# Power_managment.net
KiCad netlist of a schematic drawn in Altium Designer
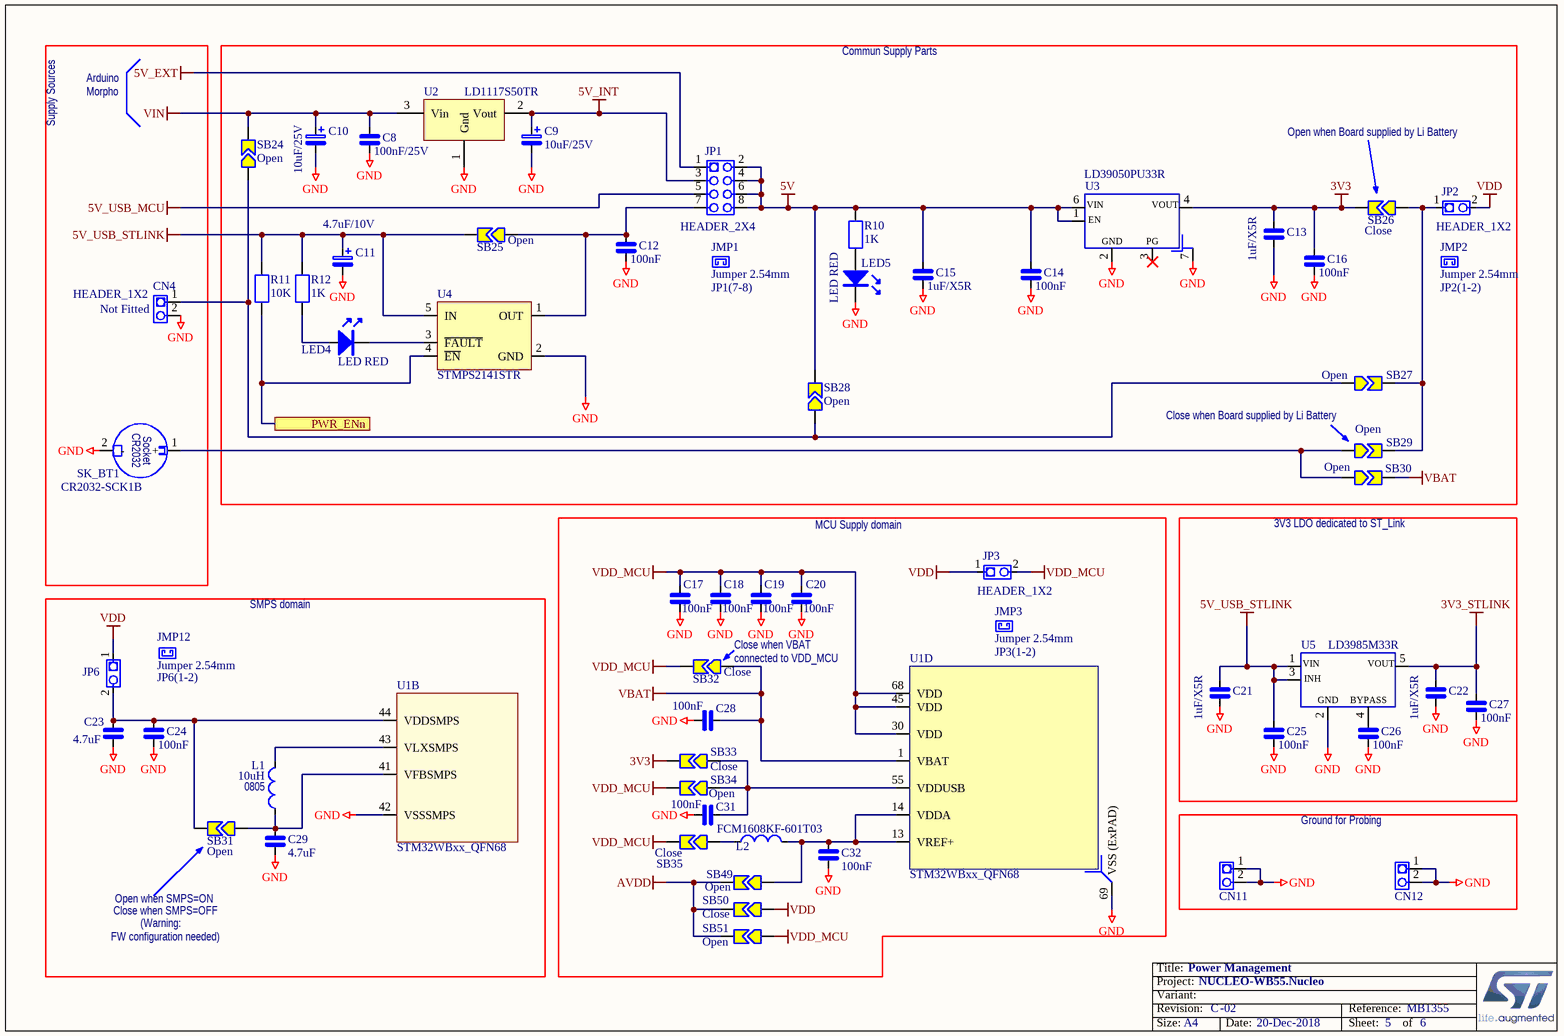
[diagram p0: Power_managment.SchDoc]

(export (version "E")
  (design (tool "Eeschema 10.0.6"))
  (components
    (comp (ref "C8")
      (value "100nF/25V")
      (footprint "0402_CAP_NPOL")
      (description "Capacitor_not polarized")
      (libsource (lib "ST_Lib3D") (part "CAP_NPOL"))
    )
    (comp (ref "C9")
      (value "10uF/25V")
      (footprint "1210_CAP_POL")
      (description "Condensateur_polarise")
      (libsource (lib "Passive") (part "CAP_POL"))
    )
    (comp (ref "C10")
      (value "10uF/25V")
      (footprint "1210_CAP_POL")
      (description "Condensateur_polarise")
      (libsource (lib "Passive") (part "CAP_POL"))
    )
    (comp (ref "C11")
      (value "4.7uF/10V")
      (footprint "1210_CAP_POL")
      (description "Condensateur_polarise")
      (libsource (lib "Passive") (part "CAP_POL"))
    )
    (comp (ref "C12")
      (value "100nF")
      (footprint "0402_CAP_NPOL")
      (description "Capacitor_not polarized")
      (libsource (lib "ST_Lib3D") (part "CAP_NPOL"))
    )
    (comp (ref "C13")
      (value "1uF/X5R")
      (footprint "0603_CAP_NPOL")
      (description "Capacitor_not polarized")
      (libsource (lib "ST_Lib3D") (part "CAP_NPOL"))
    )
    (comp (ref "C14")
      (value "100nF")
      (footprint "0402_CAP_NPOL")
      (description "Capacitor_not polarized")
      (libsource (lib "ST_Lib3D") (part "CAP_NPOL"))
    )
    (comp (ref "C15")
      (value "1uF/X5R")
      (footprint "0603_CAP_NPOL")
      (description "Capacitor_not polarized")
      (libsource (lib "ST_Lib3D") (part "CAP_NPOL"))
    )
    (comp (ref "C16")
      (value "100nF")
      (footprint "0402_CAP_NPOL")
      (description "Capacitor_not polarized")
      (libsource (lib "ST_Lib3D") (part "CAP_NPOL"))
    )
    (comp (ref "C17")
      (value "100nF")
      (footprint "0402_CAP_NPOL")
      (description "Capacitor_not polarized")
      (libsource (lib "ST_Lib3D") (part "CAP_NPOL"))
    )
    (comp (ref "C18")
      (value "100nF")
      (footprint "0402_CAP_NPOL")
      (description "Capacitor_not polarized")
      (libsource (lib "ST_Lib3D") (part "CAP_NPOL"))
    )
    (comp (ref "C19")
      (value "100nF")
      (footprint "0402_CAP_NPOL")
      (description "Capacitor_not polarized")
      (libsource (lib "ST_Lib3D") (part "CAP_NPOL"))
    )
    (comp (ref "C20")
      (value "100nF")
      (footprint "0402_CAP_NPOL")
      (description "Capacitor_not polarized")
      (libsource (lib "ST_Lib3D") (part "CAP_NPOL"))
    )
    (comp (ref "C21")
      (value "1uF/X5R")
      (footprint "0603_CAP_NPOL")
      (description "Capacitor_not polarized")
      (libsource (lib "ST_Lib3D") (part "CAP_NPOL"))
    )
    (comp (ref "C22")
      (value "1uF/X5R")
      (footprint "0603_CAP_NPOL")
      (description "Capacitor_not polarized")
      (libsource (lib "ST_Lib3D") (part "CAP_NPOL"))
    )
    (comp (ref "C23")
      (value "4.7uF")
      (footprint "0402_CAP_NPOL")
      (description "Capacitor_not polarized")
      (libsource (lib "ST_Lib3D") (part "CAP_NPOL"))
    )
    (comp (ref "C24")
      (value "100nF")
      (footprint "0402_CAP_NPOL")
      (description "Capacitor_not polarized")
      (libsource (lib "ST_Lib3D") (part "CAP_NPOL"))
    )
    (comp (ref "C25")
      (value "100nF")
      (footprint "0402_CAP_NPOL")
      (description "Capacitor_not polarized")
      (libsource (lib "ST_Lib3D") (part "CAP_NPOL"))
    )
    (comp (ref "C26")
      (value "100nF")
      (footprint "0402_CAP_NPOL")
      (description "Capacitor_not polarized")
      (libsource (lib "ST_Lib3D") (part "CAP_NPOL"))
    )
    (comp (ref "C27")
      (value "100nF")
      (footprint "0402_CAP_NPOL")
      (description "Capacitor_not polarized")
      (libsource (lib "ST_Lib3D") (part "CAP_NPOL"))
    )
    (comp (ref "C28")
      (value "100nF")
      (footprint "0402_CAP_NPOL")
      (description "Capacitor_not polarized")
      (libsource (lib "ST_Lib3D") (part "CAP_NPOL"))
    )
    (comp (ref "C29")
      (value "4.7uF")
      (footprint "0402_CAP_NPOL")
      (description "Capacitor_not polarized")
      (libsource (lib "ST_Lib3D") (part "CAP_NPOL"))
    )
    (comp (ref "C31")
      (value "100nF")
      (footprint "0402_CAP_NPOL")
      (description "Capacitor_not polarized")
      (libsource (lib "ST_Lib3D") (part "CAP_NPOL"))
    )
    (comp (ref "C32")
      (value "100nF")
      (footprint "0402_CAP_NPOL")
      (description "Capacitor_not polarized")
      (libsource (lib "ST_Lib3D") (part "CAP_NPOL"))
    )
    (comp (ref "CN4")
      (value "HEADER_1X2")
      (footprint "Header NF 1x2x2.54 TH")
      (fields (field (name "FITTED") "Not Fitted"))
      (libsource (lib "Connector") (part "HEADER_1X2"))
    )
    (comp (ref "CN11")
      (value "HEADER_1X2")
      (footprint "Header M 1x2x2.54 TH V")
      (libsource (lib "Connector") (part "HEADER_1X2"))
    )
    (comp (ref "CN12")
      (value "HEADER_1X2")
      (footprint "Header M 1x2x2.54 TH V")
      (libsource (lib "Connector") (part "HEADER_1X2"))
    )
    (comp (ref "JMP1")
      (value "Jumper 2.54mm")
      (footprint "Jumper 2.54mm BLACK")
      (fields (field (name "DEFAULT") "JP1(7-8)"))
      (libsource (lib "Connector") (part "Jumper 2.54mm"))
    )
    (comp (ref "JMP2")
      (value "Jumper 2.54mm")
      (footprint "Jumper 2.54mm BLACK")
      (fields (field (name "DEFAULT") "JP2(1-2)"))
      (libsource (lib "Connector") (part "Jumper 2.54mm"))
    )
    (comp (ref "JMP3")
      (value "Jumper 2.54mm")
      (footprint "Jumper 2.54mm BLACK")
      (fields (field (name "DEFAULT") "JP3(1-2)"))
      (libsource (lib "Connector") (part "Jumper 2.54mm"))
    )
    (comp (ref "JMP12")
      (value "Jumper 2.54mm")
      (footprint "Jumper 2.54mm BLACK")
      (fields (field (name "DEFAULT") "JP6(1-2)"))
      (libsource (lib "Connector") (part "Jumper 2.54mm"))
    )
    (comp (ref "JP1")
      (value "HEADER_2X4")
      (footprint "Header M 2x4x2.54 TH V")
      (libsource (lib "Connector") (part "HEADER_2X4"))
    )
    (comp (ref "JP2")
      (value "HEADER_1X2")
      (footprint "Header M 1x2x2.54 TH V")
      (libsource (lib "Connector") (part "HEADER_1X2_L"))
    )
    (comp (ref "JP3")
      (value "HEADER_1X2")
      (footprint "Header M 1x2x2.54 TH V")
      (libsource (lib "Connector") (part "HEADER_1X2_L"))
    )
    (comp (ref "JP6")
      (value "HEADER_1X2")
      (footprint "Header M 1x2x2.54 TH V")
      (libsource (lib "Connector") (part "HEADER_1X2_L"))
    )
    (comp (ref "L1")
      (value "10uH")
      (footprint "0805_COIL")
      (description "Coil Wurtz 10uH ref: 74479777310A")
      (libsource (lib "Passive") (part "IND_74479777310A"))
    )
    (comp (ref "L2")
      (value "FCM1608KF-601T03")
      (footprint "0603_COIL")
      (libsource (lib "Passive") (part "IND_FCM1608KF-601T03"))
    )
    (comp (ref "LED4")
      (value "LED RED")
      (footprint "0603_LED_RED")
      (description "Light-Emitting Diode")
      (libsource (lib "Active") (part "LED"))
    )
    (comp (ref "LED5")
      (value "LED RED")
      (footprint "0603_LED_RED")
      (description "Light-Emitting Diode")
      (libsource (lib "Active") (part "LED"))
    )
    (comp (ref "R10")
      (value "1K")
      (footprint "0402_RES")
      (description "Resistor")
      (libsource (lib "Lib3D_Altium10_Schlib") (part "RES"))
    )
    (comp (ref "R11")
      (value "10K")
      (footprint "0402_RES")
      (description "Resistor")
      (libsource (lib "Lib3D_Altium10_Schlib") (part "RES"))
    )
    (comp (ref "R12")
      (value "1K")
      (footprint "0402_RES")
      (description "Resistor")
      (libsource (lib "Lib3D_Altium10_Schlib") (part "RES"))
    )
    (comp (ref "SB24")
      (value "Open")
      (footprint "SB-tiny")
      (description "Solder Jumper")
      (fields (field (name "PUBLISHER") "Altium Limited"))
      (libsource (lib "Passive") (part "Strap2"))
    )
    (comp (ref "SB25")
      (value "Open")
      (footprint "SB-tiny")
      (description "Solder Jumper")
      (fields (field (name "PUBLISHER") "Altium Limited"))
      (libsource (lib "Passive") (part "Strap2"))
    )
    (comp (ref "SB26")
      (value "Close")
      (footprint "SB-tiny")
      (description "Solder Jumper")
      (fields (field (name "PUBLISHER") "Altium Limited"))
      (libsource (lib "Passive") (part "Strap2"))
    )
    (comp (ref "SB27")
      (value "Open")
      (footprint "SB-tiny")
      (description "Solder Jumper")
      (fields (field (name "PUBLISHER") "Altium Limited"))
      (libsource (lib "Passive") (part "Strap2"))
    )
    (comp (ref "SB28")
      (value "Open")
      (footprint "SB-tiny")
      (description "Solder Jumper")
      (fields (field (name "PUBLISHER") "Altium Limited"))
      (libsource (lib "Passive") (part "Strap2"))
    )
    (comp (ref "SB29")
      (value "Open")
      (footprint "SB-tiny")
      (description "Solder Jumper")
      (fields (field (name "PUBLISHER") "Altium Limited"))
      (libsource (lib "Passive") (part "Strap2"))
    )
    (comp (ref "SB30")
      (value "Open")
      (footprint "SB-tiny")
      (description "Solder Jumper")
      (fields (field (name "PUBLISHER") "Altium Limited"))
      (libsource (lib "Passive") (part "Strap2"))
    )
    (comp (ref "SB31")
      (value "Open")
      (footprint "SB-tiny")
      (description "Solder Jumper")
      (fields (field (name "PUBLISHER") "Altium Limited"))
      (libsource (lib "Passive") (part "Strap2"))
    )
    (comp (ref "SB32")
      (value "Close")
      (footprint "SB-tiny")
      (description "Solder Jumper")
      (fields (field (name "PUBLISHER") "Altium Limited"))
      (libsource (lib "Passive") (part "Strap2"))
    )
    (comp (ref "SB33")
      (value "Close")
      (footprint "SB-tiny")
      (description "Solder Jumper")
      (fields (field (name "PUBLISHER") "Altium Limited"))
      (libsource (lib "Passive") (part "Strap2"))
    )
    (comp (ref "SB34")
      (value "Open")
      (footprint "SB-tiny")
      (description "Solder Jumper")
      (fields (field (name "PUBLISHER") "Altium Limited"))
      (libsource (lib "Passive") (part "Strap2"))
    )
    (comp (ref "SB35")
      (value "Close")
      (footprint "SB-tiny")
      (description "Solder Jumper")
      (fields (field (name "PUBLISHER") "Altium Limited"))
      (libsource (lib "Passive") (part "Strap2"))
    )
    (comp (ref "SB49")
      (value "Open")
      (footprint "SB-tiny")
      (description "Solder Jumper")
      (fields (field (name "PUBLISHER") "Altium Limited"))
      (libsource (lib "Passive") (part "Strap2"))
    )
    (comp (ref "SB50")
      (value "Close")
      (footprint "SB-tiny")
      (description "Solder Jumper")
      (fields (field (name "PUBLISHER") "Altium Limited"))
      (libsource (lib "Passive") (part "Strap2"))
    )
    (comp (ref "SB51")
      (value "Open")
      (footprint "SB-tiny")
      (description "Solder Jumper")
      (fields (field (name "PUBLISHER") "Altium Limited"))
      (libsource (lib "Passive") (part "Strap2"))
    )
    (comp (ref "SK_BT1")
      (value "CR2032-SCK1B")
      (footprint "CR2032-SCK1")
      (libsource (lib "Battery_Acc_Generator") (part "CR2032-SCK1B"))
    )
    (comp (ref "U1")
      (value "STM32WBxx_QFN68")
      (footprint "VFQFPN68_8x8x0.1_p0.4")
      (libsource (lib "Active") (part "STM32WBxx_QFN68"))
    )
    (comp (ref "U2")
      (value "LD1117S50TR")
      (footprint "SOT223_SC73_A")
      (description "IC REG LDO 5V 0.8A SOT223")
      (libsource (lib "Active") (part "LD1117S50TR"))
    )
    (comp (ref "U3")
      (value "LD39050PU33R")
      (footprint "DFN6 3x3mm")
      (description "3.3V voltage regulator 500mA")
      (libsource (lib "Active") (part "LD39050PU33R"))
    )
    (comp (ref "U4")
      (value "STMPS2141STR")
      (footprint "SOT23-5")
      (description "Enhanced single channel power switches")
      (libsource (lib "Active") (part "STMPS2141STR"))
    )
    (comp (ref "U5")
      (value "LD3985M33R")
      (footprint "SOT23-5")
      (description "3.3V low drop voltage regulator")
      (fields (field (name "MANUFACTURER") "STMicroelectronics"))
      (libsource (lib "Active") (part "LD3985M33R"))
    )
  )
  (nets
    (net (code "1") (name "/PWR_ENn") (class "Default")
      (node (ref "R11") (pin "2") (pinfunction "2_2") (pintype "passive"))
      (node (ref "U4") (pin "4") (pinfunction "~{EN}_4") (pintype "passive"))
    )
    (net (code "2") (name "3V3") (class "Default")
      (node (ref "C13") (pin "1") (pinfunction "1_1") (pintype "passive"))
      (node (ref "C16") (pin "1") (pinfunction "1_1") (pintype "passive"))
      (node (ref "SB26") (pin "2") (pinfunction "2_2") (pintype "passive"))
      (node (ref "SB33") (pin "2") (pinfunction "2_2") (pintype "passive"))
      (node (ref "U3") (pin "4") (pinfunction "VOUT_4") (pintype "passive"))
    )
    (net (code "3") (name "3V3_STLINK") (class "Default")
      (node (ref "C22") (pin "1") (pinfunction "1_1") (pintype "passive"))
      (node (ref "C27") (pin "1") (pinfunction "1_1") (pintype "passive"))
      (node (ref "U5") (pin "5") (pinfunction "VOUT_5") (pintype "passive"))
    )
    (net (code "4") (name "5V") (class "Default")
      (node (ref "C14") (pin "1") (pinfunction "1_1") (pintype "passive"))
      (node (ref "C15") (pin "1") (pinfunction "1_1") (pintype "passive"))
      (node (ref "JP1") (pin "2") (pintype "passive"))
      (node (ref "JP1") (pin "4") (pintype "passive"))
      (node (ref "JP1") (pin "6") (pintype "passive"))
      (node (ref "JP1") (pin "8") (pintype "passive"))
      (node (ref "R10") (pin "1") (pinfunction "1_1") (pintype "passive"))
      (node (ref "SB28") (pin "2") (pinfunction "2_2") (pintype "passive"))
      (node (ref "U3") (pin "1") (pinfunction "EN_1") (pintype "passive"))
      (node (ref "U3") (pin "6") (pinfunction "VIN_6") (pintype "passive"))
    )
    (net (code "5") (name "5V_EXT") (class "Default") (node (ref "JP1") (pin "1") (pintype "passive")))
    (net (code "6") (name "5V_INT") (class "Default")
      (node (ref "C9") (pin "1") (pintype "passive"))
      (node (ref "JP1") (pin "3") (pintype "passive"))
      (node (ref "U2") (pin "2") (pinfunction "Vout_2") (pintype "passive"))
    )
    (net (code "7") (name "5V_USB_MCU") (class "Default") (node (ref "JP1") (pin "5") (pintype "passive")))
    (net (code "8") (name "5V_USB_STLINK") (class "Default")
      (node (ref "C11") (pin "1") (pintype "passive"))
      (node (ref "C21") (pin "1") (pinfunction "1_1") (pintype "passive"))
      (node (ref "C25") (pin "1") (pinfunction "1_1") (pintype "passive"))
      (node (ref "R11") (pin "1") (pinfunction "1_1") (pintype "passive"))
      (node (ref "R12") (pin "1") (pinfunction "1_1") (pintype "passive"))
      (node (ref "SB25") (pin "2") (pinfunction "2_2") (pintype "passive"))
      (node (ref "U4") (pin "5") (pinfunction "IN_5") (pintype "passive"))
      (node (ref "U5") (pin "1") (pinfunction "VIN_1") (pintype "passive"))
      (node (ref "U5") (pin "3") (pinfunction "CE_3") (pintype "passive"))
    )
    (net (code "9") (name "AVDD") (class "Default")
      (node (ref "SB49") (pin "2") (pinfunction "2_2") (pintype "passive"))
      (node (ref "SB50") (pin "2") (pinfunction "2_2") (pintype "passive"))
      (node (ref "SB51") (pin "2") (pinfunction "2_2") (pintype "passive"))
    )
    (net (code "10") (name "GND") (class "Default")
      (node (ref "C10") (pin "2") (pintype "passive"))
      (node (ref "C11") (pin "2") (pintype "passive"))
      (node (ref "C12") (pin "2") (pinfunction "2_2") (pintype "passive"))
      (node (ref "C13") (pin "2") (pinfunction "2_2") (pintype "passive"))
      (node (ref "C14") (pin "2") (pinfunction "2_2") (pintype "passive"))
      (node (ref "C15") (pin "2") (pinfunction "2_2") (pintype "passive"))
      (node (ref "C16") (pin "2") (pinfunction "2_2") (pintype "passive"))
      (node (ref "C17") (pin "2") (pinfunction "2_2") (pintype "passive"))
      (node (ref "C18") (pin "2") (pinfunction "2_2") (pintype "passive"))
      (node (ref "C19") (pin "2") (pinfunction "2_2") (pintype "passive"))
      (node (ref "C20") (pin "2") (pinfunction "2_2") (pintype "passive"))
      (node (ref "C21") (pin "2") (pinfunction "2_2") (pintype "passive"))
      (node (ref "C22") (pin "2") (pinfunction "2_2") (pintype "passive"))
      (node (ref "C23") (pin "2") (pinfunction "2_2") (pintype "passive"))
      (node (ref "C24") (pin "2") (pinfunction "2_2") (pintype "passive"))
      (node (ref "C25") (pin "2") (pinfunction "2_2") (pintype "passive"))
      (node (ref "C26") (pin "2") (pinfunction "2_2") (pintype "passive"))
      (node (ref "C27") (pin "2") (pinfunction "2_2") (pintype "passive"))
      (node (ref "C28") (pin "2") (pinfunction "2_2") (pintype "passive"))
      (node (ref "C29") (pin "2") (pinfunction "2_2") (pintype "passive"))
      (node (ref "C31") (pin "2") (pinfunction "2_2") (pintype "passive"))
      (node (ref "C32") (pin "2") (pinfunction "2_2") (pintype "passive"))
      (node (ref "C8") (pin "2") (pinfunction "2_2") (pintype "passive"))
      (node (ref "C9") (pin "2") (pintype "passive"))
      (node (ref "CN11") (pin "1") (pinfunction "1_1") (pintype "passive"))
      (node (ref "CN11") (pin "2") (pinfunction "2_2") (pintype "passive"))
      (node (ref "CN12") (pin "1") (pinfunction "1_1") (pintype "passive"))
      (node (ref "CN12") (pin "2") (pinfunction "2_2") (pintype "passive"))
      (node (ref "CN4") (pin "2") (pinfunction "2_2") (pintype "passive"))
      (node (ref "LED5") (pin "K") (pinfunction "K_K") (pintype "passive"))
      (node (ref "SK_BT1") (pin "2") (pinfunction "-_2") (pintype "passive"))
      (node (ref "U1") (pin "42") (pinfunction "VSSSMPS_42") (pintype "passive"))
      (node (ref "U1") (pin "69") (pinfunction "VSS_(ExPAD)_69") (pintype "passive"))
      (node (ref "U2") (pin "1") (pinfunction "Gnd_1") (pintype "passive"))
      (node (ref "U3") (pin "2") (pinfunction "VSS_2") (pintype "passive"))
      (node (ref "U3") (pin "7") (pinfunction "7_7") (pintype "passive"))
      (node (ref "U4") (pin "2") (pinfunction "GND_2") (pintype "passive"))
      (node (ref "U5") (pin "2") (pinfunction "VSS_2") (pintype "passive"))
    )
    (net (code "11") (name "Net-(CN4-Pad1)") (class "Default")
      (node (ref "CN4") (pin "1") (pinfunction "1_1") (pintype "passive"))
      (node (ref "SB24") (pin "1") (pinfunction "1_1") (pintype "passive"))
      (node (ref "SB27") (pin "1") (pinfunction "1_1") (pintype "passive"))
      (node (ref "SB28") (pin "1") (pinfunction "1_1") (pintype "passive"))
    )
    (net (code "12") (name "Net-(JP2-Pad1)") (class "Default")
      (node (ref "JP2") (pin "1") (pinfunction "1_1") (pintype "passive"))
      (node (ref "SB26") (pin "1") (pinfunction "1_1") (pintype "passive"))
      (node (ref "SB27") (pin "2") (pinfunction "2_2") (pintype "passive"))
      (node (ref "SB29") (pin "2") (pinfunction "2_2") (pintype "passive"))
    )
    (net (code "13") (name "Net-(L2-Pad1)") (class "Default")
      (node (ref "L2") (pin "1") (pinfunction "1_1") (pintype "passive"))
      (node (ref "SB35") (pin "1") (pinfunction "1_1") (pintype "passive"))
    )
    (net (code "14") (name "Net-(LED4-PadA)") (class "Default")
      (node (ref "LED4") (pin "A") (pinfunction "A_A") (pintype "passive"))
      (node (ref "R12") (pin "2") (pinfunction "2_2") (pintype "passive"))
    )
    (net (code "15") (name "Net-(LED5-PadA)") (class "Default")
      (node (ref "LED5") (pin "A") (pinfunction "A_A") (pintype "passive"))
      (node (ref "R10") (pin "2") (pinfunction "2_2") (pintype "passive"))
    )
    (net (code "16") (name "Net-(SK_BT1-+)") (class "Default")
      (node (ref "SB29") (pin "1") (pinfunction "1_1") (pintype "passive"))
      (node (ref "SB30") (pin "1") (pinfunction "1_1") (pintype "passive"))
      (node (ref "SK_BT1") (pin "1") (pinfunction "+_1") (pintype "passive"))
    )
    (net (code "17") (name "Net-(U1B-VDDSMPS)") (class "Default")
      (node (ref "C23") (pin "1") (pinfunction "1_1") (pintype "passive"))
      (node (ref "C24") (pin "1") (pinfunction "1_1") (pintype "passive"))
      (node (ref "JP6") (pin "2") (pinfunction "2_2") (pintype "passive"))
      (node (ref "SB31") (pin "2") (pinfunction "2_2") (pintype "passive"))
      (node (ref "U1") (pin "44") (pinfunction "VDDSMPS_44") (pintype "passive"))
    )
    (net (code "18") (name "Net-(U1B-VFBSMPS)") (class "Default")
      (node (ref "C29") (pin "1") (pinfunction "1_1") (pintype "passive"))
      (node (ref "L1") (pin "1") (pinfunction "1_1") (pintype "passive"))
      (node (ref "SB31") (pin "1") (pinfunction "1_1") (pintype "passive"))
      (node (ref "U1") (pin "41") (pinfunction "VFBSMPS_41") (pintype "passive"))
    )
    (net (code "19") (name "Net-(U1B-VLXSMPS)") (class "Default")
      (node (ref "L1") (pin "2") (pinfunction "2_2") (pintype "passive"))
      (node (ref "U1") (pin "43") (pinfunction "VLXSMPS_43") (pintype "passive"))
    )
    (net (code "20") (name "Net-(U1D-VDDA)") (class "Default")
      (node (ref "C32") (pin "1") (pinfunction "1_1") (pintype "passive"))
      (node (ref "L2") (pin "2") (pinfunction "2_2") (pintype "passive"))
      (node (ref "SB49") (pin "1") (pinfunction "1_1") (pintype "passive"))
      (node (ref "U1") (pin "13") (pinfunction "VREF+_13") (pintype "passive"))
      (node (ref "U1") (pin "14") (pinfunction "VDDA_14") (pintype "passive"))
    )
    (net (code "21") (name "Net-(U1D-VDDUSB)") (class "Default")
      (node (ref "C31") (pin "1") (pinfunction "1_1") (pintype "passive"))
      (node (ref "SB33") (pin "1") (pinfunction "1_1") (pintype "passive"))
      (node (ref "SB34") (pin "1") (pinfunction "1_1") (pintype "passive"))
      (node (ref "U1") (pin "55") (pinfunction "VDDUSB_55") (pintype "passive"))
    )
    (net (code "22") (name "Net-(U4-OUT)") (class "Default")
      (node (ref "C12") (pin "1") (pinfunction "1_1") (pintype "passive"))
      (node (ref "JP1") (pin "7") (pintype "passive"))
      (node (ref "SB25") (pin "1") (pinfunction "1_1") (pintype "passive"))
      (node (ref "U4") (pin "1") (pinfunction "OUT_1") (pintype "passive"))
    )
    (net (code "23") (name "Net-(U4-~{FAULT})") (class "Default")
      (node (ref "LED4") (pin "K") (pinfunction "K_K") (pintype "passive"))
      (node (ref "U4") (pin "3") (pinfunction "~{FAULT}_3") (pintype "passive"))
    )
    (net (code "24") (name "Net-(U5-BYPASS)") (class "Default")
      (node (ref "C26") (pin "1") (pinfunction "1_1") (pintype "passive"))
      (node (ref "U5") (pin "4") (pinfunction "BYPASS_4") (pintype "passive"))
    )
    (net (code "25") (name "VBAT") (class "Default")
      (node (ref "C28") (pin "1") (pinfunction "1_1") (pintype "passive"))
      (node (ref "SB30") (pin "2") (pinfunction "2_2") (pintype "passive"))
      (node (ref "SB32") (pin "1") (pinfunction "1_1") (pintype "passive"))
      (node (ref "U1") (pin "1") (pinfunction "VBAT_1") (pintype "passive"))
    )
    (net (code "26") (name "VDD") (class "Default")
      (node (ref "JP2") (pin "2") (pinfunction "2_2") (pintype "passive"))
      (node (ref "JP3") (pin "1") (pinfunction "1_1") (pintype "passive"))
      (node (ref "JP6") (pin "1") (pinfunction "1_1") (pintype "passive"))
      (node (ref "SB50") (pin "1") (pinfunction "1_1") (pintype "passive"))
    )
    (net (code "27") (name "VDD_MCU") (class "Default")
      (node (ref "C17") (pin "1") (pinfunction "1_1") (pintype "passive"))
      (node (ref "C18") (pin "1") (pinfunction "1_1") (pintype "passive"))
      (node (ref "C19") (pin "1") (pinfunction "1_1") (pintype "passive"))
      (node (ref "C20") (pin "1") (pinfunction "1_1") (pintype "passive"))
      (node (ref "JP3") (pin "2") (pinfunction "2_2") (pintype "passive"))
      (node (ref "SB32") (pin "2") (pinfunction "2_2") (pintype "passive"))
      (node (ref "SB34") (pin "2") (pinfunction "2_2") (pintype "passive"))
      (node (ref "SB35") (pin "2") (pinfunction "2_2") (pintype "passive"))
      (node (ref "SB51") (pin "1") (pinfunction "1_1") (pintype "passive"))
      (node (ref "U1") (pin "30") (pinfunction "VDD_30") (pintype "passive"))
      (node (ref "U1") (pin "45") (pinfunction "VDD_45") (pintype "passive"))
      (node (ref "U1") (pin "68") (pinfunction "VDD_68") (pintype "passive"))
    )
    (net (code "28") (name "VIN") (class "Default")
      (node (ref "C10") (pin "1") (pintype "passive"))
      (node (ref "C8") (pin "1") (pinfunction "1_1") (pintype "passive"))
      (node (ref "SB24") (pin "2") (pinfunction "2_2") (pintype "passive"))
      (node (ref "U2") (pin "3") (pinfunction "Vin_3") (pintype "passive"))
    )
    (net (code "29") (name "unconnected-(U3-PG-Pad3)") (class "Default")
      (node (ref "U3") (pin "3") (pinfunction "PG_3") (pintype "passive+no_connect"))
    )
  )
)
